# LM3404smallcapandbigcap.net
KiCad netlist of a schematic drawn in EAGLE
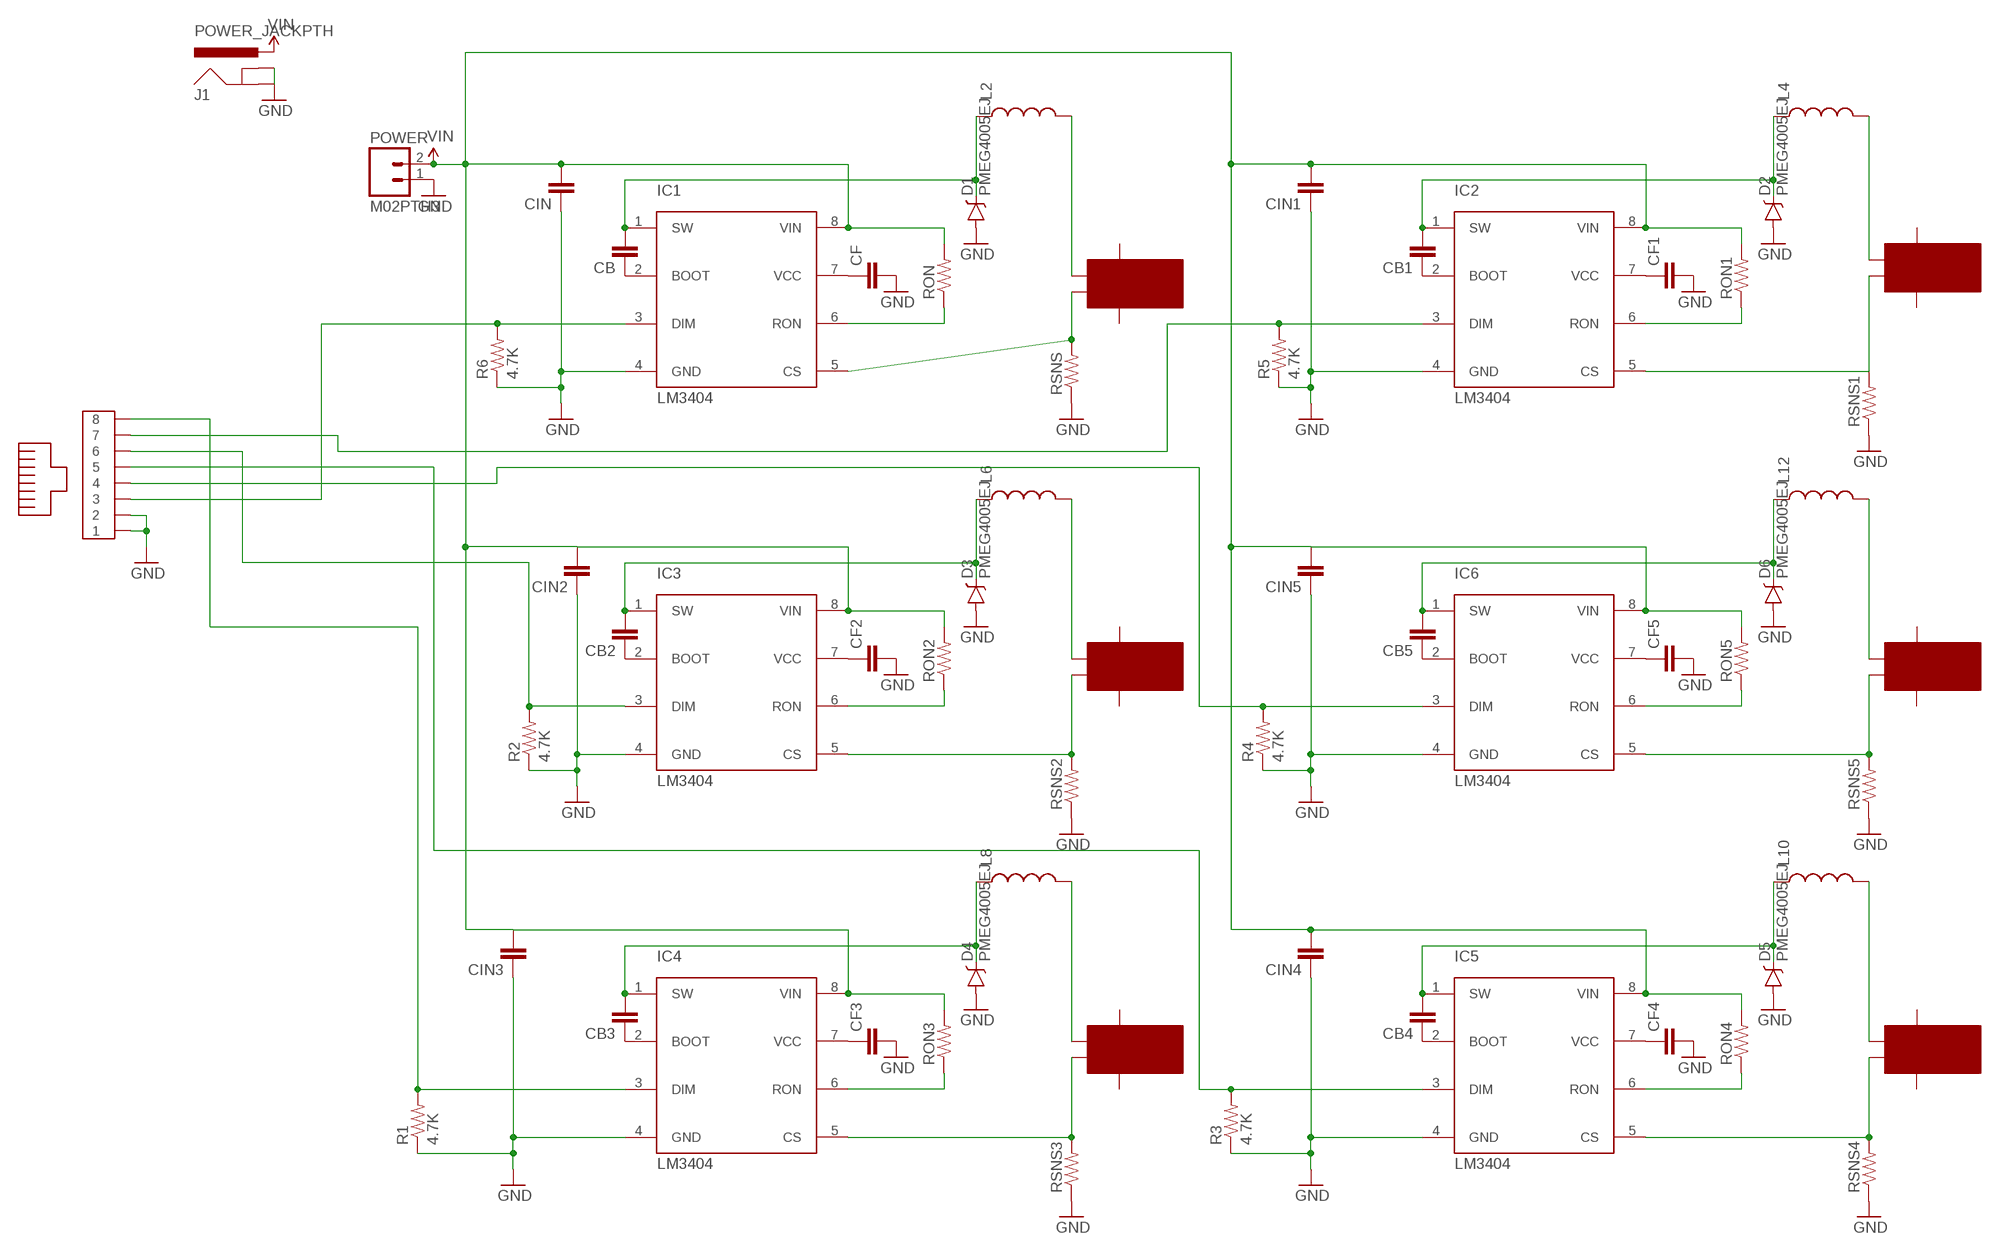
[diagram p0: schematic, sheet 1]

(export (version "E")
  (design (tool "Eeschema 10.0.6"))
  (components
    (comp (ref "CB")
      (value "CAP0603-CAP")
      (footprint "eagle-import:0603-CAP")
      (libsource (lib "eagle-import") (part "CAP0603-CAP"))
    )
    (comp (ref "CB1")
      (value "CAP0603-CAP")
      (footprint "eagle-import:0603-CAP")
      (libsource (lib "eagle-import") (part "CAP0603-CAP"))
    )
    (comp (ref "CB2")
      (value "CAP0603-CAP")
      (footprint "eagle-import:0603-CAP")
      (libsource (lib "eagle-import") (part "CAP0603-CAP"))
    )
    (comp (ref "CB3")
      (value "CAP0603-CAP")
      (footprint "eagle-import:0603-CAP")
      (libsource (lib "eagle-import") (part "CAP0603-CAP"))
    )
    (comp (ref "CB4")
      (value "CAP0603-CAP")
      (footprint "eagle-import:0603-CAP")
      (libsource (lib "eagle-import") (part "CAP0603-CAP"))
    )
    (comp (ref "CB5")
      (value "CAP0603-CAP")
      (footprint "eagle-import:0603-CAP")
      (libsource (lib "eagle-import") (part "CAP0603-CAP"))
    )
    (comp (ref "CF")
      (value "CAP1206")
      (footprint "eagle-import:1206")
      (libsource (lib "eagle-import") (part "CAP1206"))
    )
    (comp (ref "CF1")
      (value "CAP1206")
      (footprint "eagle-import:1206")
      (libsource (lib "eagle-import") (part "CAP1206"))
    )
    (comp (ref "CF2")
      (value "CAP1206")
      (footprint "eagle-import:1206")
      (libsource (lib "eagle-import") (part "CAP1206"))
    )
    (comp (ref "CF3")
      (value "CAP1206")
      (footprint "eagle-import:1206")
      (libsource (lib "eagle-import") (part "CAP1206"))
    )
    (comp (ref "CF4")
      (value "CAP1206")
      (footprint "eagle-import:1206")
      (libsource (lib "eagle-import") (part "CAP1206"))
    )
    (comp (ref "CF5")
      (value "CAP1206")
      (footprint "eagle-import:1206")
      (libsource (lib "eagle-import") (part "CAP1206"))
    )
    (comp (ref "CIN")
      (value "CAP1210")
      (footprint "eagle-import:1210")
      (libsource (lib "eagle-import") (part "CAP1210"))
    )
    (comp (ref "CIN1")
      (value "CAP1210")
      (footprint "eagle-import:1210")
      (libsource (lib "eagle-import") (part "CAP1210"))
    )
    (comp (ref "CIN2")
      (value "CAP1210")
      (footprint "eagle-import:1210")
      (libsource (lib "eagle-import") (part "CAP1210"))
    )
    (comp (ref "CIN3")
      (value "CAP1210")
      (footprint "eagle-import:1210")
      (libsource (lib "eagle-import") (part "CAP1210"))
    )
    (comp (ref "CIN4")
      (value "CAP1210")
      (footprint "eagle-import:1210")
      (libsource (lib "eagle-import") (part "CAP1210"))
    )
    (comp (ref "CIN5")
      (value "CAP1210")
      (footprint "eagle-import:1210")
      (libsource (lib "eagle-import") (part "CAP1210"))
    )
    (comp (ref "D1")
      (value "PMEG4005EJ")
      (footprint "eagle-import:SOD-323")
      (libsource (lib "eagle-import") (part "DIODE-SCHOTTKY-PMEG4005EJ"))
    )
    (comp (ref "D2")
      (value "PMEG4005EJ")
      (footprint "eagle-import:SOD-323")
      (libsource (lib "eagle-import") (part "DIODE-SCHOTTKY-PMEG4005EJ"))
    )
    (comp (ref "D3")
      (value "PMEG4005EJ")
      (footprint "eagle-import:SOD-323")
      (libsource (lib "eagle-import") (part "DIODE-SCHOTTKY-PMEG4005EJ"))
    )
    (comp (ref "D4")
      (value "PMEG4005EJ")
      (footprint "eagle-import:SOD-323")
      (libsource (lib "eagle-import") (part "DIODE-SCHOTTKY-PMEG4005EJ"))
    )
    (comp (ref "D5")
      (value "PMEG4005EJ")
      (footprint "eagle-import:SOD-323")
      (libsource (lib "eagle-import") (part "DIODE-SCHOTTKY-PMEG4005EJ"))
    )
    (comp (ref "D6")
      (value "PMEG4005EJ")
      (footprint "eagle-import:SOD-323")
      (libsource (lib "eagle-import") (part "DIODE-SCHOTTKY-PMEG4005EJ"))
    )
    (comp (ref "IC1")
      (value "LM3404")
      (footprint "eagle-import:SO8")
      (libsource (lib "eagle-import") (part "LM3404"))
    )
    (comp (ref "IC2")
      (value "LM3404")
      (footprint "eagle-import:SO8")
      (libsource (lib "eagle-import") (part "LM3404"))
    )
    (comp (ref "IC3")
      (value "LM3404")
      (footprint "eagle-import:SO8")
      (libsource (lib "eagle-import") (part "LM3404"))
    )
    (comp (ref "IC4")
      (value "LM3404")
      (footprint "eagle-import:SO8")
      (libsource (lib "eagle-import") (part "LM3404"))
    )
    (comp (ref "IC5")
      (value "LM3404")
      (footprint "eagle-import:SO8")
      (libsource (lib "eagle-import") (part "LM3404"))
    )
    (comp (ref "IC6")
      (value "LM3404")
      (footprint "eagle-import:SO8")
      (libsource (lib "eagle-import") (part "LM3404"))
    )
    (comp (ref "J1")
      (value "POWER_JACKPTH")
      (footprint "eagle-import:POWER_JACK_PTH")
      (libsource (lib "eagle-import") (part "POWER_JACKPTH"))
    )
    (comp (ref "L2")
      (value "INDUCTORSDR1105")
      (footprint "eagle-import:B82462G")
      (libsource (lib "eagle-import") (part "INDUCTORSDR1105"))
    )
    (comp (ref "L4")
      (value "INDUCTORSDR1105")
      (footprint "eagle-import:B82462G")
      (libsource (lib "eagle-import") (part "INDUCTORSDR1105"))
    )
    (comp (ref "L6")
      (value "INDUCTORSDR1105")
      (footprint "eagle-import:B82462G")
      (libsource (lib "eagle-import") (part "INDUCTORSDR1105"))
    )
    (comp (ref "L8")
      (value "INDUCTORSDR1105")
      (footprint "eagle-import:B82462G")
      (libsource (lib "eagle-import") (part "INDUCTORSDR1105"))
    )
    (comp (ref "L10")
      (value "INDUCTORSDR1105")
      (footprint "eagle-import:B82462G")
      (libsource (lib "eagle-import") (part "INDUCTORSDR1105"))
    )
    (comp (ref "L12")
      (value "INDUCTORSDR1105")
      (footprint "eagle-import:B82462G")
      (libsource (lib "eagle-import") (part "INDUCTORSDR1105"))
    )
    (comp (ref "POWER")
      (value "M02PTH3")
      (footprint "eagle-import:1X02_LONGPADS")
      (libsource (lib "eagle-import") (part "M02PTH3"))
    )
    (comp (ref "R1")
      (value "4.7K")
      (footprint "eagle-import:1206")
      (libsource (lib "eagle-import") (part "RESISTOR1206"))
    )
    (comp (ref "R2")
      (value "4.7K")
      (footprint "eagle-import:1206")
      (libsource (lib "eagle-import") (part "RESISTOR1206"))
    )
    (comp (ref "R3")
      (value "4.7K")
      (footprint "eagle-import:1206")
      (libsource (lib "eagle-import") (part "RESISTOR1206"))
    )
    (comp (ref "R4")
      (value "4.7K")
      (footprint "eagle-import:1206")
      (libsource (lib "eagle-import") (part "RESISTOR1206"))
    )
    (comp (ref "R5")
      (value "4.7K")
      (footprint "eagle-import:1206")
      (libsource (lib "eagle-import") (part "RESISTOR1206"))
    )
    (comp (ref "R6")
      (value "4.7K")
      (footprint "eagle-import:1206")
      (libsource (lib "eagle-import") (part "RESISTOR1206"))
    )
    (comp (ref "RON")
      (value "RESISTOR1206")
      (footprint "eagle-import:1206")
      (libsource (lib "eagle-import") (part "RESISTOR1206"))
    )
    (comp (ref "RON1")
      (value "RESISTOR1206")
      (footprint "eagle-import:1206")
      (libsource (lib "eagle-import") (part "RESISTOR1206"))
    )
    (comp (ref "RON2")
      (value "RESISTOR1206")
      (footprint "eagle-import:1206")
      (libsource (lib "eagle-import") (part "RESISTOR1206"))
    )
    (comp (ref "RON3")
      (value "RESISTOR1206")
      (footprint "eagle-import:1206")
      (libsource (lib "eagle-import") (part "RESISTOR1206"))
    )
    (comp (ref "RON4")
      (value "RESISTOR1206")
      (footprint "eagle-import:1206")
      (libsource (lib "eagle-import") (part "RESISTOR1206"))
    )
    (comp (ref "RON5")
      (value "RESISTOR1206")
      (footprint "eagle-import:1206")
      (libsource (lib "eagle-import") (part "RESISTOR1206"))
    )
    (comp (ref "RSNS")
      (value "RESISTOR1206")
      (footprint "eagle-import:1206")
      (libsource (lib "eagle-import") (part "RESISTOR1206"))
    )
    (comp (ref "RSNS1")
      (value "RESISTOR1206")
      (footprint "eagle-import:1206")
      (libsource (lib "eagle-import") (part "RESISTOR1206"))
    )
    (comp (ref "RSNS2")
      (value "RESISTOR1206")
      (footprint "eagle-import:1206")
      (libsource (lib "eagle-import") (part "RESISTOR1206"))
    )
    (comp (ref "RSNS3")
      (value "RESISTOR1206")
      (footprint "eagle-import:1206")
      (libsource (lib "eagle-import") (part "RESISTOR1206"))
    )
    (comp (ref "RSNS4")
      (value "RESISTOR1206")
      (footprint "eagle-import:1206")
      (libsource (lib "eagle-import") (part "RESISTOR1206"))
    )
    (comp (ref "RSNS5")
      (value "RESISTOR1206")
      (footprint "eagle-import:1206")
      (libsource (lib "eagle-import") (part "RESISTOR1206"))
    )
    (comp (ref "U$1")
      (value "MOLEX-RJ45-SMT")
      (footprint "eagle-import:MOLEX-RJ45-SMT")
      (libsource (lib "eagle-import") (part "MOLEX-RJ45-SMT"))
    )
    (comp (ref "U$2")
      (value "RCA_JACK")
      (footprint "eagle-import:RCA_JACK")
      (libsource (lib "eagle-import") (part "RCA_JACK"))
    )
    (comp (ref "U$3")
      (value "RCA_JACK")
      (footprint "eagle-import:RCA_JACK")
      (libsource (lib "eagle-import") (part "RCA_JACK"))
    )
    (comp (ref "U$4")
      (value "RCA_JACK")
      (footprint "eagle-import:RCA_JACK")
      (libsource (lib "eagle-import") (part "RCA_JACK"))
    )
    (comp (ref "U$5")
      (value "RCA_JACK")
      (footprint "eagle-import:RCA_JACK")
      (libsource (lib "eagle-import") (part "RCA_JACK"))
    )
    (comp (ref "U$6")
      (value "RCA_JACK")
      (footprint "eagle-import:RCA_JACK")
      (libsource (lib "eagle-import") (part "RCA_JACK"))
    )
    (comp (ref "U$7")
      (value "RCA_JACK")
      (footprint "eagle-import:RCA_JACK")
      (libsource (lib "eagle-import") (part "RCA_JACK"))
    )
  )
  (nets
    (net (code "1") (name "GND") (class "Default")
      (node (ref "CF") (pin "2") (pinfunction "2_2") (pintype "passive"))
      (node (ref "CF1") (pin "2") (pinfunction "2_2") (pintype "passive"))
      (node (ref "CF2") (pin "2") (pinfunction "2_2") (pintype "passive"))
      (node (ref "CF3") (pin "2") (pinfunction "2_2") (pintype "passive"))
      (node (ref "CF4") (pin "2") (pinfunction "2_2") (pintype "passive"))
      (node (ref "CF5") (pin "2") (pinfunction "2_2") (pintype "passive"))
      (node (ref "CIN") (pin "1") (pinfunction "1_1") (pintype "passive"))
      (node (ref "CIN1") (pin "1") (pinfunction "1_1") (pintype "passive"))
      (node (ref "CIN2") (pin "1") (pinfunction "1_1") (pintype "passive"))
      (node (ref "CIN3") (pin "1") (pinfunction "1_1") (pintype "passive"))
      (node (ref "CIN4") (pin "1") (pinfunction "1_1") (pintype "passive"))
      (node (ref "CIN5") (pin "1") (pinfunction "1_1") (pintype "passive"))
      (node (ref "D1") (pin "A") (pinfunction "A_A") (pintype "passive"))
      (node (ref "D2") (pin "A") (pinfunction "A_A") (pintype "passive"))
      (node (ref "D3") (pin "A") (pinfunction "A_A") (pintype "passive"))
      (node (ref "D4") (pin "A") (pinfunction "A_A") (pintype "passive"))
      (node (ref "D5") (pin "A") (pinfunction "A_A") (pintype "passive"))
      (node (ref "D6") (pin "A") (pinfunction "A_A") (pintype "passive"))
      (node (ref "IC1") (pin "4") (pinfunction "GND_4") (pintype "bidirectional"))
      (node (ref "IC2") (pin "4") (pinfunction "GND_4") (pintype "bidirectional"))
      (node (ref "IC3") (pin "4") (pinfunction "GND_4") (pintype "bidirectional"))
      (node (ref "IC4") (pin "4") (pinfunction "GND_4") (pintype "bidirectional"))
      (node (ref "IC5") (pin "4") (pinfunction "GND_4") (pintype "bidirectional"))
      (node (ref "IC6") (pin "4") (pinfunction "GND_4") (pintype "bidirectional"))
      (node (ref "J1") (pin "GND") (pinfunction "GND_GND") (pintype "bidirectional"))
      (node (ref "J1") (pin "GNDBREAK") (pinfunction "GNDBREAK_GNDBREAK") (pintype "bidirectional"))
      (node (ref "POWER") (pin "1") (pinfunction "1_1") (pintype "passive"))
      (node (ref "R1") (pin "1") (pinfunction "1_1") (pintype "passive"))
      (node (ref "R2") (pin "1") (pinfunction "1_1") (pintype "passive"))
      (node (ref "R3") (pin "1") (pinfunction "1_1") (pintype "passive"))
      (node (ref "R4") (pin "1") (pinfunction "1_1") (pintype "passive"))
      (node (ref "R5") (pin "1") (pinfunction "1_1") (pintype "passive"))
      (node (ref "R6") (pin "1") (pinfunction "1_1") (pintype "passive"))
      (node (ref "RSNS") (pin "1") (pinfunction "1_1") (pintype "passive"))
      (node (ref "RSNS1") (pin "1") (pinfunction "1_1") (pintype "passive"))
      (node (ref "RSNS2") (pin "1") (pinfunction "1_1") (pintype "passive"))
      (node (ref "RSNS3") (pin "1") (pinfunction "1_1") (pintype "passive"))
      (node (ref "RSNS4") (pin "1") (pinfunction "1_1") (pintype "passive"))
      (node (ref "RSNS5") (pin "1") (pinfunction "1_1") (pintype "passive"))
      (node (ref "U$1") (pin "1") (pinfunction "1_1") (pintype "bidirectional"))
      (node (ref "U$1") (pin "2") (pinfunction "2_2") (pintype "bidirectional"))
    )
    (net (code "2") (name "Net-(IC1-BOOT)") (class "Default")
      (node (ref "CB") (pin "1") (pinfunction "1_1") (pintype "passive"))
      (node (ref "IC1") (pin "2") (pinfunction "BOOT_2") (pintype "bidirectional"))
    )
    (net (code "3") (name "Net-(IC1-CS)") (class "Default")
      (node (ref "IC1") (pin "5") (pinfunction "CS_5") (pintype "bidirectional"))
      (node (ref "RSNS") (pin "2") (pinfunction "2_2") (pintype "passive"))
      (node (ref "U$7") (pin "INNER") (pinfunction "INNER_INNER") (pintype "bidirectional"))
    )
    (net (code "4") (name "Net-(IC1-DIM)") (class "Default")
      (node (ref "IC1") (pin "3") (pinfunction "DIM_3") (pintype "bidirectional"))
      (node (ref "R6") (pin "2") (pinfunction "2_2") (pintype "passive"))
      (node (ref "U$1") (pin "3") (pinfunction "3_3") (pintype "bidirectional"))
    )
    (net (code "5") (name "Net-(IC1-RON)") (class "Default")
      (node (ref "IC1") (pin "6") (pinfunction "RON_6") (pintype "bidirectional"))
      (node (ref "RON") (pin "1") (pinfunction "1_1") (pintype "passive"))
    )
    (net (code "6") (name "Net-(IC1-SW)") (class "Default")
      (node (ref "CB") (pin "2") (pinfunction "2_2") (pintype "passive"))
      (node (ref "D1") (pin "C") (pinfunction "C_C") (pintype "passive"))
      (node (ref "IC1") (pin "1") (pinfunction "SW_1") (pintype "bidirectional"))
      (node (ref "L2") (pin "P$1") (pinfunction "1_P$1") (pintype "passive"))
    )
    (net (code "7") (name "Net-(IC1-VCC)") (class "Default")
      (node (ref "CF") (pin "1") (pinfunction "1_1") (pintype "passive"))
      (node (ref "IC1") (pin "7") (pinfunction "VCC_7") (pintype "bidirectional"))
    )
    (net (code "8") (name "Net-(IC2-BOOT)") (class "Default")
      (node (ref "CB1") (pin "1") (pinfunction "1_1") (pintype "passive"))
      (node (ref "IC2") (pin "2") (pinfunction "BOOT_2") (pintype "bidirectional"))
    )
    (net (code "9") (name "Net-(IC2-CS)") (class "Default")
      (node (ref "IC2") (pin "5") (pinfunction "CS_5") (pintype "bidirectional"))
      (node (ref "RSNS1") (pin "2") (pinfunction "2_2") (pintype "passive"))
      (node (ref "U$2") (pin "INNER") (pinfunction "INNER_INNER") (pintype "bidirectional"))
    )
    (net (code "10") (name "Net-(IC2-DIM)") (class "Default")
      (node (ref "IC2") (pin "3") (pinfunction "DIM_3") (pintype "bidirectional"))
      (node (ref "R5") (pin "2") (pinfunction "2_2") (pintype "passive"))
      (node (ref "U$1") (pin "7") (pinfunction "7_7") (pintype "bidirectional"))
    )
    (net (code "11") (name "Net-(IC2-RON)") (class "Default")
      (node (ref "IC2") (pin "6") (pinfunction "RON_6") (pintype "bidirectional"))
      (node (ref "RON1") (pin "1") (pinfunction "1_1") (pintype "passive"))
    )
    (net (code "12") (name "Net-(IC2-SW)") (class "Default")
      (node (ref "CB1") (pin "2") (pinfunction "2_2") (pintype "passive"))
      (node (ref "D2") (pin "C") (pinfunction "C_C") (pintype "passive"))
      (node (ref "IC2") (pin "1") (pinfunction "SW_1") (pintype "bidirectional"))
      (node (ref "L4") (pin "P$1") (pinfunction "1_P$1") (pintype "passive"))
    )
    (net (code "13") (name "Net-(IC2-VCC)") (class "Default")
      (node (ref "CF1") (pin "1") (pinfunction "1_1") (pintype "passive"))
      (node (ref "IC2") (pin "7") (pinfunction "VCC_7") (pintype "bidirectional"))
    )
    (net (code "14") (name "Net-(IC3-BOOT)") (class "Default")
      (node (ref "CB2") (pin "1") (pinfunction "1_1") (pintype "passive"))
      (node (ref "IC3") (pin "2") (pinfunction "BOOT_2") (pintype "bidirectional"))
    )
    (net (code "15") (name "Net-(IC3-CS)") (class "Default")
      (node (ref "IC3") (pin "5") (pinfunction "CS_5") (pintype "bidirectional"))
      (node (ref "RSNS2") (pin "2") (pinfunction "2_2") (pintype "passive"))
      (node (ref "U$6") (pin "INNER") (pinfunction "INNER_INNER") (pintype "bidirectional"))
    )
    (net (code "16") (name "Net-(IC3-DIM)") (class "Default")
      (node (ref "IC3") (pin "3") (pinfunction "DIM_3") (pintype "bidirectional"))
      (node (ref "R2") (pin "2") (pinfunction "2_2") (pintype "passive"))
      (node (ref "U$1") (pin "6") (pinfunction "6_6") (pintype "bidirectional"))
    )
    (net (code "17") (name "Net-(IC3-RON)") (class "Default")
      (node (ref "IC3") (pin "6") (pinfunction "RON_6") (pintype "bidirectional"))
      (node (ref "RON2") (pin "1") (pinfunction "1_1") (pintype "passive"))
    )
    (net (code "18") (name "Net-(IC3-SW)") (class "Default")
      (node (ref "CB2") (pin "2") (pinfunction "2_2") (pintype "passive"))
      (node (ref "D3") (pin "C") (pinfunction "C_C") (pintype "passive"))
      (node (ref "IC3") (pin "1") (pinfunction "SW_1") (pintype "bidirectional"))
      (node (ref "L6") (pin "P$1") (pinfunction "1_P$1") (pintype "passive"))
    )
    (net (code "19") (name "Net-(IC3-VCC)") (class "Default")
      (node (ref "CF2") (pin "1") (pinfunction "1_1") (pintype "passive"))
      (node (ref "IC3") (pin "7") (pinfunction "VCC_7") (pintype "bidirectional"))
    )
    (net (code "20") (name "Net-(IC4-BOOT)") (class "Default")
      (node (ref "CB3") (pin "1") (pinfunction "1_1") (pintype "passive"))
      (node (ref "IC4") (pin "2") (pinfunction "BOOT_2") (pintype "bidirectional"))
    )
    (net (code "21") (name "Net-(IC4-CS)") (class "Default")
      (node (ref "IC4") (pin "5") (pinfunction "CS_5") (pintype "bidirectional"))
      (node (ref "RSNS3") (pin "2") (pinfunction "2_2") (pintype "passive"))
      (node (ref "U$5") (pin "INNER") (pinfunction "INNER_INNER") (pintype "bidirectional"))
    )
    (net (code "22") (name "Net-(IC4-DIM)") (class "Default")
      (node (ref "IC4") (pin "3") (pinfunction "DIM_3") (pintype "bidirectional"))
      (node (ref "R1") (pin "2") (pinfunction "2_2") (pintype "passive"))
      (node (ref "U$1") (pin "8") (pinfunction "8_8") (pintype "bidirectional"))
    )
    (net (code "23") (name "Net-(IC4-RON)") (class "Default")
      (node (ref "IC4") (pin "6") (pinfunction "RON_6") (pintype "bidirectional"))
      (node (ref "RON3") (pin "1") (pinfunction "1_1") (pintype "passive"))
    )
    (net (code "24") (name "Net-(IC4-SW)") (class "Default")
      (node (ref "CB3") (pin "2") (pinfunction "2_2") (pintype "passive"))
      (node (ref "D4") (pin "C") (pinfunction "C_C") (pintype "passive"))
      (node (ref "IC4") (pin "1") (pinfunction "SW_1") (pintype "bidirectional"))
      (node (ref "L8") (pin "P$1") (pinfunction "1_P$1") (pintype "passive"))
    )
    (net (code "25") (name "Net-(IC4-VCC)") (class "Default")
      (node (ref "CF3") (pin "1") (pinfunction "1_1") (pintype "passive"))
      (node (ref "IC4") (pin "7") (pinfunction "VCC_7") (pintype "bidirectional"))
    )
    (net (code "26") (name "Net-(IC5-BOOT)") (class "Default")
      (node (ref "CB4") (pin "1") (pinfunction "1_1") (pintype "passive"))
      (node (ref "IC5") (pin "2") (pinfunction "BOOT_2") (pintype "bidirectional"))
    )
    (net (code "27") (name "Net-(IC5-CS)") (class "Default")
      (node (ref "IC5") (pin "5") (pinfunction "CS_5") (pintype "bidirectional"))
      (node (ref "RSNS4") (pin "2") (pinfunction "2_2") (pintype "passive"))
      (node (ref "U$4") (pin "INNER") (pinfunction "INNER_INNER") (pintype "bidirectional"))
    )
    (net (code "28") (name "Net-(IC5-DIM)") (class "Default")
      (node (ref "IC5") (pin "3") (pinfunction "DIM_3") (pintype "bidirectional"))
      (node (ref "R3") (pin "2") (pinfunction "2_2") (pintype "passive"))
      (node (ref "U$1") (pin "5") (pinfunction "5_5") (pintype "bidirectional"))
    )
    (net (code "29") (name "Net-(IC5-RON)") (class "Default")
      (node (ref "IC5") (pin "6") (pinfunction "RON_6") (pintype "bidirectional"))
      (node (ref "RON4") (pin "1") (pinfunction "1_1") (pintype "passive"))
    )
    (net (code "30") (name "Net-(IC5-SW)") (class "Default")
      (node (ref "CB4") (pin "2") (pinfunction "2_2") (pintype "passive"))
      (node (ref "D5") (pin "C") (pinfunction "C_C") (pintype "passive"))
      (node (ref "IC5") (pin "1") (pinfunction "SW_1") (pintype "bidirectional"))
      (node (ref "L10") (pin "P$1") (pinfunction "1_P$1") (pintype "passive"))
    )
    (net (code "31") (name "Net-(IC5-VCC)") (class "Default")
      (node (ref "CF4") (pin "1") (pinfunction "1_1") (pintype "passive"))
      (node (ref "IC5") (pin "7") (pinfunction "VCC_7") (pintype "bidirectional"))
    )
    (net (code "32") (name "Net-(IC6-BOOT)") (class "Default")
      (node (ref "CB5") (pin "1") (pinfunction "1_1") (pintype "passive"))
      (node (ref "IC6") (pin "2") (pinfunction "BOOT_2") (pintype "bidirectional"))
    )
    (net (code "33") (name "Net-(IC6-CS)") (class "Default")
      (node (ref "IC6") (pin "5") (pinfunction "CS_5") (pintype "bidirectional"))
      (node (ref "RSNS5") (pin "2") (pinfunction "2_2") (pintype "passive"))
      (node (ref "U$3") (pin "INNER") (pinfunction "INNER_INNER") (pintype "bidirectional"))
    )
    (net (code "34") (name "Net-(IC6-DIM)") (class "Default")
      (node (ref "IC6") (pin "3") (pinfunction "DIM_3") (pintype "bidirectional"))
      (node (ref "R4") (pin "2") (pinfunction "2_2") (pintype "passive"))
      (node (ref "U$1") (pin "4") (pinfunction "4_4") (pintype "bidirectional"))
    )
    (net (code "35") (name "Net-(IC6-RON)") (class "Default")
      (node (ref "IC6") (pin "6") (pinfunction "RON_6") (pintype "bidirectional"))
      (node (ref "RON5") (pin "1") (pinfunction "1_1") (pintype "passive"))
    )
    (net (code "36") (name "Net-(IC6-SW)") (class "Default")
      (node (ref "CB5") (pin "2") (pinfunction "2_2") (pintype "passive"))
      (node (ref "D6") (pin "C") (pinfunction "C_C") (pintype "passive"))
      (node (ref "IC6") (pin "1") (pinfunction "SW_1") (pintype "bidirectional"))
      (node (ref "L12") (pin "P$1") (pinfunction "1_P$1") (pintype "passive"))
    )
    (net (code "37") (name "Net-(IC6-VCC)") (class "Default")
      (node (ref "CF5") (pin "1") (pinfunction "1_1") (pintype "passive"))
      (node (ref "IC6") (pin "7") (pinfunction "VCC_7") (pintype "bidirectional"))
    )
    (net (code "38") (name "Net-(L2-2)") (class "Default")
      (node (ref "L2") (pin "P$2") (pinfunction "2_P$2") (pintype "passive"))
      (node (ref "U$7") (pin "SIG") (pinfunction "SIG_SIG") (pintype "bidirectional"))
    )
    (net (code "39") (name "Net-(L4-2)") (class "Default")
      (node (ref "L4") (pin "P$2") (pinfunction "2_P$2") (pintype "passive"))
      (node (ref "U$2") (pin "SIG") (pinfunction "SIG_SIG") (pintype "bidirectional"))
    )
    (net (code "40") (name "Net-(L6-2)") (class "Default")
      (node (ref "L6") (pin "P$2") (pinfunction "2_P$2") (pintype "passive"))
      (node (ref "U$6") (pin "SIG") (pinfunction "SIG_SIG") (pintype "bidirectional"))
    )
    (net (code "41") (name "Net-(L8-2)") (class "Default")
      (node (ref "L8") (pin "P$2") (pinfunction "2_P$2") (pintype "passive"))
      (node (ref "U$5") (pin "SIG") (pinfunction "SIG_SIG") (pintype "bidirectional"))
    )
    (net (code "42") (name "Net-(L10-2)") (class "Default")
      (node (ref "L10") (pin "P$2") (pinfunction "2_P$2") (pintype "passive"))
      (node (ref "U$4") (pin "SIG") (pinfunction "SIG_SIG") (pintype "bidirectional"))
    )
    (net (code "43") (name "Net-(L12-2)") (class "Default")
      (node (ref "L12") (pin "P$2") (pinfunction "2_P$2") (pintype "passive"))
      (node (ref "U$3") (pin "SIG") (pinfunction "SIG_SIG") (pintype "bidirectional"))
    )
    (net (code "44") (name "VIN") (class "Default")
      (node (ref "CIN") (pin "2") (pinfunction "2_2") (pintype "passive"))
      (node (ref "CIN1") (pin "2") (pinfunction "2_2") (pintype "passive"))
      (node (ref "CIN2") (pin "2") (pinfunction "2_2") (pintype "passive"))
      (node (ref "CIN3") (pin "2") (pinfunction "2_2") (pintype "passive"))
      (node (ref "CIN4") (pin "2") (pinfunction "2_2") (pintype "passive"))
      (node (ref "CIN5") (pin "2") (pinfunction "2_2") (pintype "passive"))
      (node (ref "IC1") (pin "8") (pinfunction "VIN_8") (pintype "bidirectional"))
      (node (ref "IC2") (pin "8") (pinfunction "VIN_8") (pintype "bidirectional"))
      (node (ref "IC3") (pin "8") (pinfunction "VIN_8") (pintype "bidirectional"))
      (node (ref "IC4") (pin "8") (pinfunction "VIN_8") (pintype "bidirectional"))
      (node (ref "IC5") (pin "8") (pinfunction "VIN_8") (pintype "bidirectional"))
      (node (ref "IC6") (pin "8") (pinfunction "VIN_8") (pintype "bidirectional"))
      (node (ref "J1") (pin "PWR") (pinfunction "PWR_PWR") (pintype "bidirectional"))
      (node (ref "POWER") (pin "2") (pinfunction "2_2") (pintype "passive"))
      (node (ref "RON") (pin "2") (pinfunction "2_2") (pintype "passive"))
      (node (ref "RON1") (pin "2") (pinfunction "2_2") (pintype "passive"))
      (node (ref "RON2") (pin "2") (pinfunction "2_2") (pintype "passive"))
      (node (ref "RON3") (pin "2") (pinfunction "2_2") (pintype "passive"))
      (node (ref "RON4") (pin "2") (pinfunction "2_2") (pintype "passive"))
      (node (ref "RON5") (pin "2") (pinfunction "2_2") (pintype "passive"))
    )
    (net (code "45") (name "unconnected-(U$2-PadSWA)") (class "Default")
      (node (ref "U$2") (pin "SWA") (pinfunction "SWA_SWA") (pintype "bidirectional"))
    )
    (net (code "46") (name "unconnected-(U$2-PadSWB)") (class "Default")
      (node (ref "U$2") (pin "SWB") (pinfunction "SWB_SWB") (pintype "bidirectional"))
    )
    (net (code "47") (name "unconnected-(U$3-PadSWA)") (class "Default")
      (node (ref "U$3") (pin "SWA") (pinfunction "SWA_SWA") (pintype "bidirectional"))
    )
    (net (code "48") (name "unconnected-(U$3-PadSWB)") (class "Default")
      (node (ref "U$3") (pin "SWB") (pinfunction "SWB_SWB") (pintype "bidirectional"))
    )
    (net (code "49") (name "unconnected-(U$4-PadSWA)") (class "Default")
      (node (ref "U$4") (pin "SWA") (pinfunction "SWA_SWA") (pintype "bidirectional"))
    )
    (net (code "50") (name "unconnected-(U$4-PadSWB)") (class "Default")
      (node (ref "U$4") (pin "SWB") (pinfunction "SWB_SWB") (pintype "bidirectional"))
    )
    (net (code "51") (name "unconnected-(U$5-PadSWA)") (class "Default")
      (node (ref "U$5") (pin "SWA") (pinfunction "SWA_SWA") (pintype "bidirectional"))
    )
    (net (code "52") (name "unconnected-(U$5-PadSWB)") (class "Default")
      (node (ref "U$5") (pin "SWB") (pinfunction "SWB_SWB") (pintype "bidirectional"))
    )
    (net (code "53") (name "unconnected-(U$6-PadSWA)") (class "Default")
      (node (ref "U$6") (pin "SWA") (pinfunction "SWA_SWA") (pintype "bidirectional"))
    )
    (net (code "54") (name "unconnected-(U$6-PadSWB)") (class "Default")
      (node (ref "U$6") (pin "SWB") (pinfunction "SWB_SWB") (pintype "bidirectional"))
    )
    (net (code "55") (name "unconnected-(U$7-PadSWA)") (class "Default")
      (node (ref "U$7") (pin "SWA") (pinfunction "SWA_SWA") (pintype "bidirectional"))
    )
    (net (code "56") (name "unconnected-(U$7-PadSWB)") (class "Default")
      (node (ref "U$7") (pin "SWB") (pinfunction "SWB_SWB") (pintype "bidirectional"))
    )
  )
)
